# Input_block.net
KiCad netlist of a schematic drawn in Altium Designer
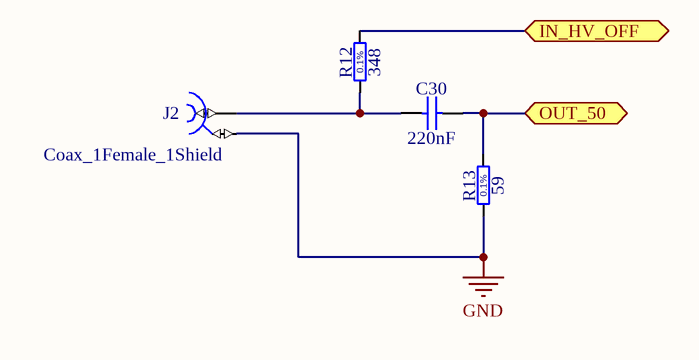
[diagram p0: Input_block.SchDoc]

(export (version "E")
  (design (tool "Eeschema 10.0.6"))
  (components
    (comp (ref "C30")
      (value "220nF")
      (footprint "CAPC2012X135N")
      (description "Non-polarised capacitor")
      (fields
        (field (name "PART NUMBER") "CC0805_220NF_50V_10%_X7R")
        (field (name "VOLTAGE") "50V")
        (field (name "AUTHOR") "CERN DEM JLC")
      )
      (libsource (lib "Capacitors") (part "Capacitor - non polarized"))
    )
    (comp (ref "J2")
      (value "Coax_1Female_1Shield")
      (footprint "SAMTEC_MMCX-J-P-H-ST-TH1")
      (fields
        (field (name "PART NUMBER") "SAMTEC_MMCX-J-P-H-ST-TH1")
        (field (name "MANUFACTURER") "SAMTEC")
        (field (name "MANUFACTURER PART NUMBER") "MMCX-J-P-H-ST-TH1")
        (field (name "AUTHOR") "CERN DEM JLC")
      )
      (libsource (lib "Connectors") (part "Coax_1Female_1Shield"))
    )
    (comp (ref "R12")
      (value "348")
      (footprint "RESC2012X60N")
      (description "Resistor - 0.1%")
      (fields
        (field (name "PART NUMBER") "R0805_348R_0.1%_0.1W_10PPM")
        (field (name "POWER") "0.1W")
        (field (name "AUTHOR") "CERN DEM JLC")
      )
      (libsource (lib "Resistors") (part "Resistor - 0.1%"))
    )
    (comp (ref "R13")
      (value "59")
      (footprint "RESC2012X60N")
      (description "Resistor - 0.1%")
      (fields
        (field (name "PART NUMBER") "R0805_59R_0.1%_0.1W_10PPM")
        (field (name "POWER") "0.1W")
        (field (name "AUTHOR") "CERN DEM JLC")
      )
      (libsource (lib "Resistors") (part "Resistor - 0.1%"))
    )
  )
  (nets
    (net (code "1") (name "/IN_HV_OFF") (class "Default")
      (node (ref "R12") (pin "2") (pinfunction "2_2") (pintype "passive"))
    )
    (net (code "2") (name "/OUT_50") (class "Default")
      (node (ref "C30") (pin "2") (pinfunction "2_2") (pintype "passive"))
      (node (ref "R13") (pin "2") (pinfunction "2_2") (pintype "passive"))
    )
    (net (code "3") (name "GND") (class "Default")
      (node (ref "J2") (pin "2") (pinfunction "2_2") (pintype "bidirectional"))
      (node (ref "R13") (pin "1") (pinfunction "1_1") (pintype "passive"))
    )
    (net (code "4") (name "Net-(C30-Pad1)") (class "Default")
      (node (ref "C30") (pin "1") (pinfunction "1_1") (pintype "passive"))
      (node (ref "J2") (pin "1") (pinfunction "1_1") (pintype "bidirectional"))
      (node (ref "R12") (pin "1") (pinfunction "1_1") (pintype "passive"))
    )
  )
)
